# Lab2.net
KiCad netlist of a schematic drawn in EAGLE
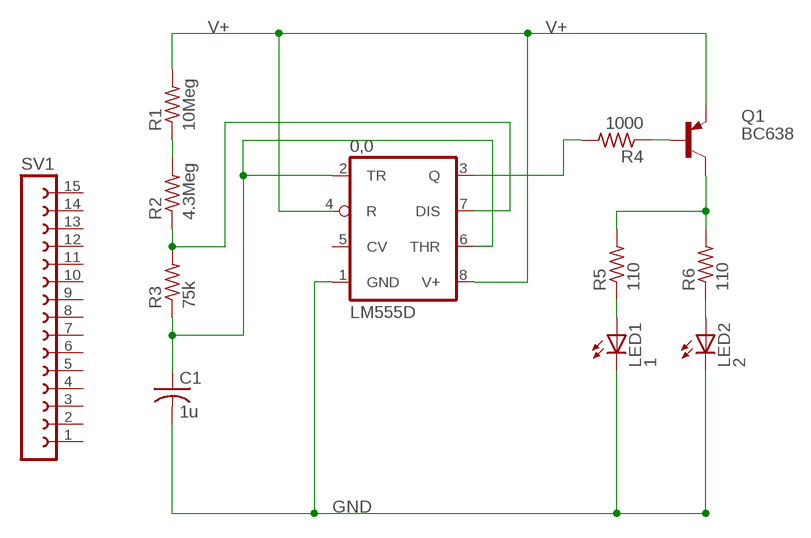
[diagram p0: schematic, sheet 1]
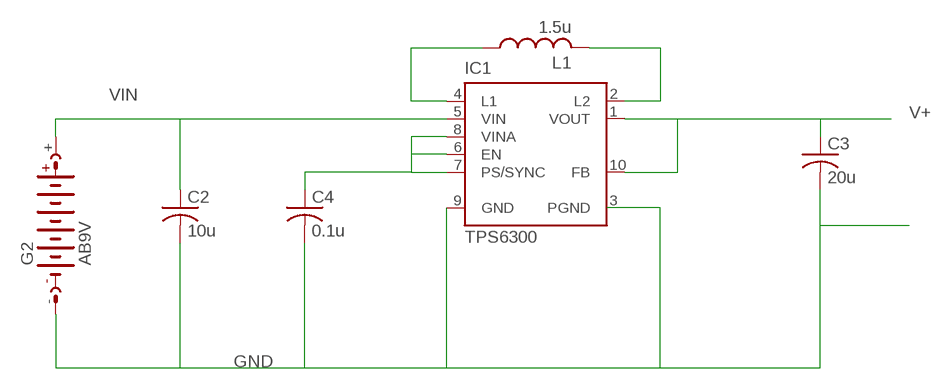
[diagram p1: schematic, sheet 2]

(export (version "E")
  (design (tool "Eeschema 10.0.6"))
  (components
    (comp (ref "C2")
      (value "10u")
      (footprint "eagle-import:C1206")
      (libsource (lib "eagle-import") (part "C-USC1206"))
    )
    (comp (ref "C3")
      (value "20u")
      (footprint "eagle-import:C1206")
      (libsource (lib "eagle-import") (part "C-USC1206"))
    )
    (comp (ref "C4")
      (value "0.1u")
      (footprint "eagle-import:C1206")
      (libsource (lib "eagle-import") (part "C-USC1206"))
    )
    (comp (ref "G2")
      (value "AB9V")
      (footprint "eagle-import:AB9V")
      (libsource (lib "eagle-import") (part "AB9V"))
    )
    (comp (ref "IC1")
      (value "TPS6300")
      (footprint "eagle-import:DRC-S-PVSON-N10")
      (fields (field (name "MPN") "TPS63000DRCTG4"))
      (libsource (lib "eagle-import") (part "TPS6300"))
    )
    (comp (ref "L1")
      (value "1.5u")
      (footprint "eagle-import:L4035M")
      (libsource (lib "eagle-import") (part "L-USL4035M"))
    )
    (comp (ref "0,0")
      (value "LM555D")
      (footprint "eagle-import:SO08")
      (libsource (lib "eagle-import") (part "555DLM"))
    )
    (comp (ref "C1")
      (value "1u")
      (footprint "eagle-import:C1206")
      (libsource (lib "eagle-import") (part "C-USC1206"))
    )
    (comp (ref "LED1")
      (value "1")
      (footprint "eagle-import:LED3MM")
      (libsource (lib "eagle-import") (part "LED3MM"))
    )
    (comp (ref "LED2")
      (value "2")
      (footprint "eagle-import:LED3MM")
      (libsource (lib "eagle-import") (part "LED3MM"))
    )
    (comp (ref "Q1")
      (value "BC638")
      (footprint "eagle-import:TO92-BCE")
      (libsource (lib "eagle-import") (part "BC638"))
    )
    (comp (ref "R1")
      (value "10Meg")
      (footprint "eagle-import:M0805")
      (libsource (lib "eagle-import") (part "R-US_M0805"))
    )
    (comp (ref "R2")
      (value "4.3Meg")
      (footprint "eagle-import:M0805")
      (libsource (lib "eagle-import") (part "R-US_M0805"))
    )
    (comp (ref "R3")
      (value "75k")
      (footprint "eagle-import:M0805")
      (libsource (lib "eagle-import") (part "R-US_M0805"))
    )
    (comp (ref "R4")
      (value "1000")
      (footprint "eagle-import:M0805")
      (libsource (lib "eagle-import") (part "R-US_M0805"))
    )
    (comp (ref "R5")
      (value "110")
      (footprint "eagle-import:M0805")
      (libsource (lib "eagle-import") (part "R-US_M0805"))
    )
    (comp (ref "R6")
      (value "110")
      (footprint "eagle-import:M0805")
      (libsource (lib "eagle-import") (part "R-US_M0805"))
    )
    (comp (ref "SV1")
      (value "FE15-1")
      (footprint "eagle-import:FE15")
      (libsource (lib "eagle-import") (part "FE15-1"))
    )
  )
  (nets
    (net (code "1") (name "GND") (class "Default")
      (node (ref "0,0") (pin "1") (pinfunction "GND_1") (pintype "power_in"))
      (node (ref "C1") (pin "2") (pinfunction "2_2") (pintype "passive"))
      (node (ref "C2") (pin "2") (pinfunction "2_2") (pintype "passive"))
      (node (ref "C3") (pin "2") (pinfunction "2_2") (pintype "passive"))
      (node (ref "C4") (pin "2") (pinfunction "2_2") (pintype "passive"))
      (node (ref "G2") (pin "-") (pinfunction "-_-") (pintype "passive"))
      (node (ref "IC1") (pin "9") (pinfunction "GND_9") (pintype "power_in"))
      (node (ref "LED1") (pin "K") (pinfunction "C_K") (pintype "passive"))
      (node (ref "LED2") (pin "K") (pinfunction "C_K") (pintype "passive"))
    )
    (net (code "2") (name "Net-(0,0-DIS)") (class "Default")
      (node (ref "0,0") (pin "7") (pinfunction "DIS_7") (pintype "input"))
      (node (ref "R2") (pin "1") (pinfunction "1_1") (pintype "passive"))
      (node (ref "R3") (pin "2") (pinfunction "2_2") (pintype "passive"))
    )
    (net (code "3") (name "Net-(0,0-Q)") (class "Default")
      (node (ref "0,0") (pin "3") (pinfunction "Q_3") (pintype "output"))
      (node (ref "R4") (pin "2") (pinfunction "2_2") (pintype "passive"))
    )
    (net (code "4") (name "Net-(0,0-THR)") (class "Default")
      (node (ref "0,0") (pin "2") (pinfunction "TR_2") (pintype "input"))
      (node (ref "0,0") (pin "6") (pinfunction "THR_6") (pintype "input"))
      (node (ref "C1") (pin "1") (pinfunction "1_1") (pintype "passive"))
      (node (ref "R3") (pin "1") (pinfunction "1_1") (pintype "passive"))
    )
    (net (code "5") (name "Net-(IC1A-EN)") (class "Default")
      (node (ref "C4") (pin "1") (pinfunction "1_1") (pintype "passive"))
      (node (ref "IC1") (pin "6") (pinfunction "EN_6") (pintype "input"))
      (node (ref "IC1") (pin "7") (pinfunction "PS/SYNC_7") (pintype "input"))
      (node (ref "IC1") (pin "8") (pinfunction "VINA_8") (pintype "input"))
    )
    (net (code "6") (name "Net-(IC1A-L1)") (class "Default")
      (node (ref "IC1") (pin "4") (pinfunction "L1_4") (pintype "passive"))
      (node (ref "L1") (pin "1") (pinfunction "1_1") (pintype "passive"))
    )
    (net (code "7") (name "Net-(IC1A-L2)") (class "Default")
      (node (ref "IC1") (pin "2") (pinfunction "L2_2") (pintype "passive"))
      (node (ref "L1") (pin "2") (pinfunction "2_2") (pintype "passive"))
    )
    (net (code "8") (name "Net-(LED1-PadA)") (class "Default")
      (node (ref "LED1") (pin "A") (pinfunction "A_A") (pintype "passive"))
      (node (ref "R5") (pin "1") (pinfunction "1_1") (pintype "passive"))
    )
    (net (code "9") (name "Net-(LED2-PadA)") (class "Default")
      (node (ref "LED2") (pin "A") (pinfunction "A_A") (pintype "passive"))
      (node (ref "R6") (pin "1") (pinfunction "1_1") (pintype "passive"))
    )
    (net (code "10") (name "Net-(Q1-PadB)") (class "Default")
      (node (ref "Q1") (pin "B") (pinfunction "B_B") (pintype "passive"))
      (node (ref "R4") (pin "1") (pinfunction "1_1") (pintype "passive"))
    )
    (net (code "11") (name "Net-(Q1-PadC)") (class "Default")
      (node (ref "Q1") (pin "C") (pinfunction "C_C") (pintype "passive"))
      (node (ref "R5") (pin "2") (pinfunction "2_2") (pintype "passive"))
      (node (ref "R6") (pin "2") (pinfunction "2_2") (pintype "passive"))
    )
    (net (code "12") (name "Net-(R1-Pad1)") (class "Default")
      (node (ref "R1") (pin "1") (pinfunction "1_1") (pintype "passive"))
      (node (ref "R2") (pin "2") (pinfunction "2_2") (pintype "passive"))
    )
    (net (code "13") (name "PGND") (class "Default")
      (node (ref "IC1") (pin "3") (pinfunction "PGND_3") (pintype "power_in"))
    )
    (net (code "14") (name "V+") (class "Default")
      (node (ref "0,0") (pin "4") (pinfunction "R_4") (pintype "input"))
      (node (ref "0,0") (pin "8") (pinfunction "V+_8") (pintype "power_in"))
      (node (ref "C3") (pin "1") (pinfunction "1_1") (pintype "passive"))
      (node (ref "IC1") (pin "1") (pinfunction "VOUT_1") (pintype "output"))
      (node (ref "IC1") (pin "10") (pinfunction "FB_10") (pintype "input"))
      (node (ref "Q1") (pin "E") (pinfunction "E_E") (pintype "passive"))
      (node (ref "R1") (pin "2") (pinfunction "2_2") (pintype "passive"))
    )
    (net (code "15") (name "VIN") (class "Default")
      (node (ref "C2") (pin "1") (pinfunction "1_1") (pintype "passive"))
      (node (ref "G2") (pin "+") (pinfunction "+_+") (pintype "passive"))
      (node (ref "IC1") (pin "5") (pinfunction "VIN_5") (pintype "input"))
    )
    (net (code "16") (name "unconnected-(0,0-CV-Pad5)") (class "Default")
      (node (ref "0,0") (pin "5") (pinfunction "CV_5") (pintype "input"))
    )
    (net (code "17") (name "unconnected-(SV1-Pad1)") (class "Default")
      (node (ref "SV1") (pin "1") (pinfunction "1_1") (pintype "passive"))
    )
    (net (code "18") (name "unconnected-(SV1-Pad2)") (class "Default")
      (node (ref "SV1") (pin "2") (pinfunction "2_2") (pintype "passive"))
    )
    (net (code "19") (name "unconnected-(SV1-Pad3)") (class "Default")
      (node (ref "SV1") (pin "3") (pinfunction "3_3") (pintype "passive"))
    )
    (net (code "20") (name "unconnected-(SV1-Pad4)") (class "Default")
      (node (ref "SV1") (pin "4") (pinfunction "4_4") (pintype "passive"))
    )
    (net (code "21") (name "unconnected-(SV1-Pad5)") (class "Default")
      (node (ref "SV1") (pin "5") (pinfunction "5_5") (pintype "passive"))
    )
    (net (code "22") (name "unconnected-(SV1-Pad6)") (class "Default")
      (node (ref "SV1") (pin "6") (pinfunction "6_6") (pintype "passive"))
    )
    (net (code "23") (name "unconnected-(SV1-Pad7)") (class "Default")
      (node (ref "SV1") (pin "7") (pinfunction "7_7") (pintype "passive"))
    )
    (net (code "24") (name "unconnected-(SV1-Pad8)") (class "Default")
      (node (ref "SV1") (pin "8") (pinfunction "8_8") (pintype "passive"))
    )
    (net (code "25") (name "unconnected-(SV1-Pad9)") (class "Default")
      (node (ref "SV1") (pin "9") (pinfunction "9_9") (pintype "passive"))
    )
    (net (code "26") (name "unconnected-(SV1-Pad10)") (class "Default")
      (node (ref "SV1") (pin "10") (pinfunction "10_10") (pintype "passive"))
    )
    (net (code "27") (name "unconnected-(SV1-Pad11)") (class "Default")
      (node (ref "SV1") (pin "11") (pinfunction "11_11") (pintype "passive"))
    )
    (net (code "28") (name "unconnected-(SV1-Pad12)") (class "Default")
      (node (ref "SV1") (pin "12") (pinfunction "12_12") (pintype "passive"))
    )
    (net (code "29") (name "unconnected-(SV1-Pad13)") (class "Default")
      (node (ref "SV1") (pin "13") (pinfunction "13_13") (pintype "passive"))
    )
    (net (code "30") (name "unconnected-(SV1-Pad14)") (class "Default")
      (node (ref "SV1") (pin "14") (pinfunction "14_14") (pintype "passive"))
    )
    (net (code "31") (name "unconnected-(SV1-Pad15)") (class "Default")
      (node (ref "SV1") (pin "15") (pinfunction "15_15") (pintype "passive"))
    )
  )
)
